# Sheet1.net
KiCad netlist of a schematic drawn in Altium Designer
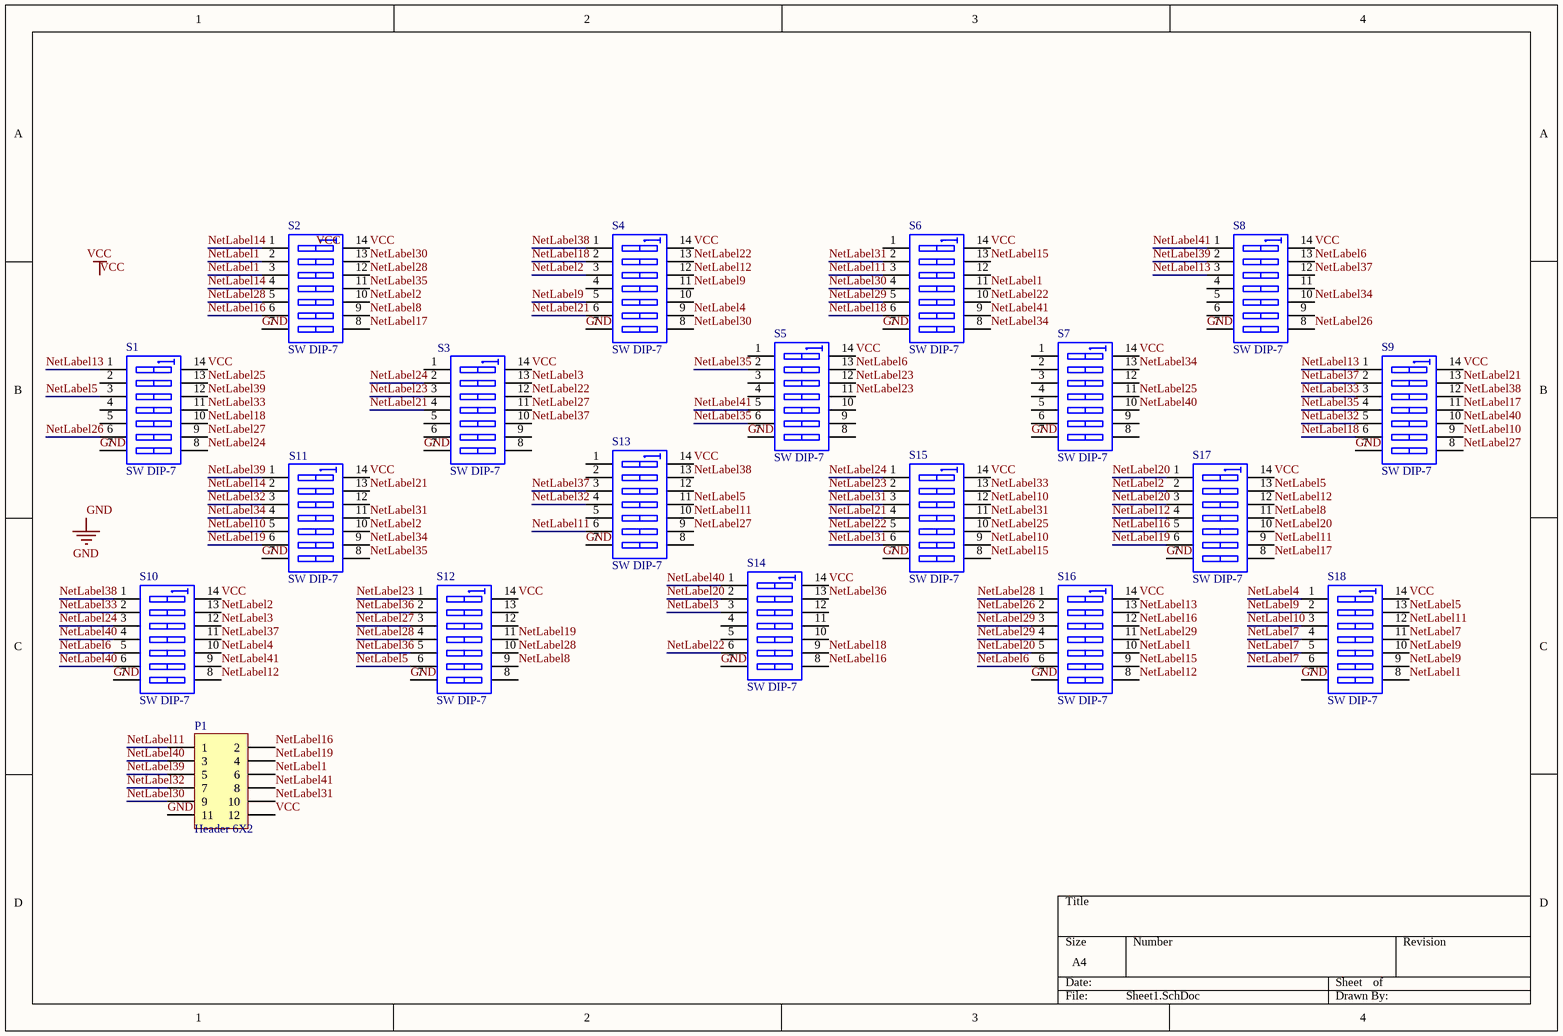
[diagram p0: Sheet1.SchDoc]

(export (version "E")
  (design (tool "Eeschema 10.0.6"))
  (components
    (comp (ref "P1")
      (value "Header 6X2")
      (footprint "HDR2X6")
      (description "Header, 6-Pin, Dual row")
      (fields (field (name "PUBLISHER") "Altium Limited"))
      (libsource (lib "Miscellaneous Connectors") (part "Header 6X2"))
    )
    (comp (ref "S1")
      (value "SW DIP-7")
      (footprint "DIP-14")
      (description "DIP Switch, 7 Position, SPST")
      (fields (field (name "PUBLISHER") "Altium Limited"))
      (libsource (lib "Miscellaneous Devices") (part "SW DIP-7"))
    )
    (comp (ref "S2")
      (value "SW DIP-7")
      (footprint "DIP-14")
      (description "DIP Switch, 7 Position, SPST")
      (fields (field (name "PUBLISHER") "Altium Limited"))
      (libsource (lib "Miscellaneous Devices") (part "SW DIP-7"))
    )
    (comp (ref "S3")
      (value "SW DIP-7")
      (footprint "DIP-14")
      (description "DIP Switch, 7 Position, SPST")
      (fields (field (name "PUBLISHER") "Altium Limited"))
      (libsource (lib "Miscellaneous Devices") (part "SW DIP-7"))
    )
    (comp (ref "S4")
      (value "SW DIP-7")
      (footprint "DIP-14")
      (description "DIP Switch, 7 Position, SPST")
      (fields (field (name "PUBLISHER") "Altium Limited"))
      (libsource (lib "Miscellaneous Devices") (part "SW DIP-7"))
    )
    (comp (ref "S5")
      (value "SW DIP-7")
      (footprint "DIP-14")
      (description "DIP Switch, 7 Position, SPST")
      (fields (field (name "PUBLISHER") "Altium Limited"))
      (libsource (lib "Miscellaneous Devices") (part "SW DIP-7"))
    )
    (comp (ref "S6")
      (value "SW DIP-7")
      (footprint "DIP-14")
      (description "DIP Switch, 7 Position, SPST")
      (fields (field (name "PUBLISHER") "Altium Limited"))
      (libsource (lib "Miscellaneous Devices") (part "SW DIP-7"))
    )
    (comp (ref "S7")
      (value "SW DIP-7")
      (footprint "DIP-14")
      (description "DIP Switch, 7 Position, SPST")
      (fields (field (name "PUBLISHER") "Altium Limited"))
      (libsource (lib "Miscellaneous Devices") (part "SW DIP-7"))
    )
    (comp (ref "S8")
      (value "SW DIP-7")
      (footprint "DIP-14")
      (description "DIP Switch, 7 Position, SPST")
      (fields (field (name "PUBLISHER") "Altium Limited"))
      (libsource (lib "Miscellaneous Devices") (part "SW DIP-7"))
    )
    (comp (ref "S9")
      (value "SW DIP-7")
      (footprint "DIP-14")
      (description "DIP Switch, 7 Position, SPST")
      (fields (field (name "PUBLISHER") "Altium Limited"))
      (libsource (lib "Miscellaneous Devices") (part "SW DIP-7"))
    )
    (comp (ref "S10")
      (value "SW DIP-7")
      (footprint "DIP-14")
      (description "DIP Switch, 7 Position, SPST")
      (fields (field (name "PUBLISHER") "Altium Limited"))
      (libsource (lib "Miscellaneous Devices") (part "SW DIP-7"))
    )
    (comp (ref "S11")
      (value "SW DIP-7")
      (footprint "DIP-14")
      (description "DIP Switch, 7 Position, SPST")
      (fields (field (name "PUBLISHER") "Altium Limited"))
      (libsource (lib "Miscellaneous Devices") (part "SW DIP-7"))
    )
    (comp (ref "S12")
      (value "SW DIP-7")
      (footprint "DIP-14")
      (description "DIP Switch, 7 Position, SPST")
      (fields (field (name "PUBLISHER") "Altium Limited"))
      (libsource (lib "Miscellaneous Devices") (part "SW DIP-7"))
    )
    (comp (ref "S13")
      (value "SW DIP-7")
      (footprint "DIP-14")
      (description "DIP Switch, 7 Position, SPST")
      (fields (field (name "PUBLISHER") "Altium Limited"))
      (libsource (lib "Miscellaneous Devices") (part "SW DIP-7"))
    )
    (comp (ref "S14")
      (value "SW DIP-7")
      (footprint "DIP-14")
      (description "DIP Switch, 7 Position, SPST")
      (fields (field (name "PUBLISHER") "Altium Limited"))
      (libsource (lib "Miscellaneous Devices") (part "SW DIP-7"))
    )
    (comp (ref "S15")
      (value "SW DIP-7")
      (footprint "DIP-14")
      (description "DIP Switch, 7 Position, SPST")
      (fields (field (name "PUBLISHER") "Altium Limited"))
      (libsource (lib "Miscellaneous Devices") (part "SW DIP-7"))
    )
    (comp (ref "S16")
      (value "SW DIP-7")
      (footprint "DIP-14")
      (description "DIP Switch, 7 Position, SPST")
      (fields (field (name "PUBLISHER") "Altium Limited"))
      (libsource (lib "Miscellaneous Devices") (part "SW DIP-7"))
    )
    (comp (ref "S17")
      (value "SW DIP-7")
      (footprint "DIP-14")
      (description "DIP Switch, 7 Position, SPST")
      (fields (field (name "PUBLISHER") "Altium Limited"))
      (libsource (lib "Miscellaneous Devices") (part "SW DIP-7"))
    )
    (comp (ref "S18")
      (value "SW DIP-7")
      (footprint "DIP-14")
      (description "DIP Switch, 7 Position, SPST")
      (fields (field (name "PUBLISHER") "Altium Limited"))
      (libsource (lib "Miscellaneous Devices") (part "SW DIP-7"))
    )
  )
  (nets
    (net (code "1") (name "/NetLabel1") (class "Default")
      (node (ref "P1") (pin "6") (pinfunction "6_6") (pintype "passive"))
      (node (ref "S16") (pin "10") (pinfunction "B5_10") (pintype "passive"))
      (node (ref "S18") (pin "8") (pinfunction "B7_8") (pintype "passive"))
      (node (ref "S2") (pin "2") (pinfunction "A2_2") (pintype "passive"))
      (node (ref "S2") (pin "3") (pinfunction "A3_3") (pintype "passive"))
      (node (ref "S6") (pin "11") (pinfunction "B4_11") (pintype "passive"))
    )
    (net (code "2") (name "/NetLabel2") (class "Default")
      (node (ref "S10") (pin "13") (pinfunction "B2_13") (pintype "passive"))
      (node (ref "S11") (pin "10") (pinfunction "B5_10") (pintype "passive"))
      (node (ref "S17") (pin "2") (pinfunction "A2_2") (pintype "passive"))
      (node (ref "S2") (pin "10") (pinfunction "B5_10") (pintype "passive"))
      (node (ref "S4") (pin "3") (pinfunction "A3_3") (pintype "passive"))
    )
    (net (code "3") (name "/NetLabel3") (class "Default")
      (node (ref "S10") (pin "12") (pinfunction "B3_12") (pintype "passive"))
      (node (ref "S14") (pin "3") (pinfunction "A3_3") (pintype "passive"))
      (node (ref "S3") (pin "13") (pinfunction "B2_13") (pintype "passive"))
    )
    (net (code "4") (name "/NetLabel4") (class "Default")
      (node (ref "S10") (pin "10") (pinfunction "B5_10") (pintype "passive"))
      (node (ref "S18") (pin "1") (pinfunction "A1_1") (pintype "passive"))
      (node (ref "S4") (pin "9") (pinfunction "B6_9") (pintype "passive"))
    )
    (net (code "5") (name "/NetLabel5") (class "Default")
      (node (ref "S1") (pin "3") (pinfunction "A3_3") (pintype "passive"))
      (node (ref "S12") (pin "6") (pinfunction "A6_6") (pintype "passive"))
      (node (ref "S13") (pin "11") (pinfunction "B4_11") (pintype "passive"))
      (node (ref "S17") (pin "13") (pinfunction "B2_13") (pintype "passive"))
      (node (ref "S18") (pin "13") (pinfunction "B2_13") (pintype "passive"))
    )
    (net (code "6") (name "/NetLabel6") (class "Default")
      (node (ref "S10") (pin "5") (pinfunction "A5_5") (pintype "passive"))
      (node (ref "S16") (pin "6") (pinfunction "A6_6") (pintype "passive"))
      (node (ref "S5") (pin "13") (pinfunction "B2_13") (pintype "passive"))
      (node (ref "S8") (pin "13") (pinfunction "B2_13") (pintype "passive"))
    )
    (net (code "7") (name "/NetLabel7") (class "Default")
      (node (ref "S18") (pin "11") (pinfunction "B4_11") (pintype "passive"))
      (node (ref "S18") (pin "4") (pinfunction "A4_4") (pintype "passive"))
      (node (ref "S18") (pin "5") (pinfunction "A5_5") (pintype "passive"))
      (node (ref "S18") (pin "6") (pinfunction "A6_6") (pintype "passive"))
    )
    (net (code "8") (name "/NetLabel8") (class "Default")
      (node (ref "S12") (pin "9") (pinfunction "B6_9") (pintype "passive"))
      (node (ref "S17") (pin "11") (pinfunction "B4_11") (pintype "passive"))
      (node (ref "S2") (pin "9") (pinfunction "B6_9") (pintype "passive"))
    )
    (net (code "9") (name "/NetLabel9") (class "Default")
      (node (ref "S18") (pin "10") (pinfunction "B5_10") (pintype "passive"))
      (node (ref "S18") (pin "2") (pinfunction "A2_2") (pintype "passive"))
      (node (ref "S18") (pin "9") (pinfunction "B6_9") (pintype "passive"))
      (node (ref "S4") (pin "11") (pinfunction "B4_11") (pintype "passive"))
      (node (ref "S4") (pin "5") (pinfunction "A5_5") (pintype "passive"))
    )
    (net (code "10") (name "/NetLabel10") (class "Default")
      (node (ref "S11") (pin "5") (pinfunction "A5_5") (pintype "passive"))
      (node (ref "S15") (pin "12") (pinfunction "B3_12") (pintype "passive"))
      (node (ref "S15") (pin "9") (pinfunction "B6_9") (pintype "passive"))
      (node (ref "S18") (pin "3") (pinfunction "A3_3") (pintype "passive"))
      (node (ref "S9") (pin "9") (pinfunction "B6_9") (pintype "passive"))
    )
    (net (code "11") (name "/NetLabel11") (class "Default")
      (node (ref "P1") (pin "1") (pinfunction "1_1") (pintype "passive"))
      (node (ref "S13") (pin "10") (pinfunction "B5_10") (pintype "passive"))
      (node (ref "S13") (pin "6") (pinfunction "A6_6") (pintype "passive"))
      (node (ref "S17") (pin "9") (pinfunction "B6_9") (pintype "passive"))
      (node (ref "S18") (pin "12") (pinfunction "B3_12") (pintype "passive"))
      (node (ref "S6") (pin "3") (pinfunction "A3_3") (pintype "passive"))
    )
    (net (code "12") (name "/NetLabel12") (class "Default")
      (node (ref "S10") (pin "8") (pinfunction "B7_8") (pintype "passive"))
      (node (ref "S16") (pin "8") (pinfunction "B7_8") (pintype "passive"))
      (node (ref "S17") (pin "12") (pinfunction "B3_12") (pintype "passive"))
      (node (ref "S17") (pin "4") (pinfunction "A4_4") (pintype "passive"))
      (node (ref "S4") (pin "12") (pinfunction "B3_12") (pintype "passive"))
    )
    (net (code "13") (name "/NetLabel13") (class "Default")
      (node (ref "S1") (pin "1") (pinfunction "A1_1") (pintype "passive"))
      (node (ref "S16") (pin "13") (pinfunction "B2_13") (pintype "passive"))
      (node (ref "S8") (pin "3") (pinfunction "A3_3") (pintype "passive"))
      (node (ref "S9") (pin "1") (pinfunction "A1_1") (pintype "passive"))
    )
    (net (code "14") (name "/NetLabel14") (class "Default")
      (node (ref "S11") (pin "2") (pinfunction "A2_2") (pintype "passive"))
      (node (ref "S2") (pin "1") (pinfunction "A1_1") (pintype "passive"))
      (node (ref "S2") (pin "4") (pinfunction "A4_4") (pintype "passive"))
    )
    (net (code "15") (name "/NetLabel15") (class "Default")
      (node (ref "S15") (pin "8") (pinfunction "B7_8") (pintype "passive"))
      (node (ref "S16") (pin "9") (pinfunction "B6_9") (pintype "passive"))
      (node (ref "S6") (pin "13") (pinfunction "B2_13") (pintype "passive"))
    )
    (net (code "16") (name "/NetLabel16") (class "Default")
      (node (ref "P1") (pin "2") (pinfunction "2_2") (pintype "passive"))
      (node (ref "S14") (pin "8") (pinfunction "B7_8") (pintype "passive"))
      (node (ref "S16") (pin "12") (pinfunction "B3_12") (pintype "passive"))
      (node (ref "S17") (pin "5") (pinfunction "A5_5") (pintype "passive"))
      (node (ref "S2") (pin "6") (pinfunction "A6_6") (pintype "passive"))
    )
    (net (code "17") (name "/NetLabel17") (class "Default")
      (node (ref "S17") (pin "8") (pinfunction "B7_8") (pintype "passive"))
      (node (ref "S2") (pin "8") (pinfunction "B7_8") (pintype "passive"))
      (node (ref "S9") (pin "11") (pinfunction "B4_11") (pintype "passive"))
    )
    (net (code "18") (name "/NetLabel18") (class "Default")
      (node (ref "S1") (pin "10") (pinfunction "B5_10") (pintype "passive"))
      (node (ref "S14") (pin "9") (pinfunction "B6_9") (pintype "passive"))
      (node (ref "S4") (pin "2") (pinfunction "A2_2") (pintype "passive"))
      (node (ref "S6") (pin "6") (pinfunction "A6_6") (pintype "passive"))
      (node (ref "S9") (pin "6") (pinfunction "A6_6") (pintype "passive"))
    )
    (net (code "19") (name "/NetLabel19") (class "Default")
      (node (ref "P1") (pin "4") (pinfunction "4_4") (pintype "passive"))
      (node (ref "S11") (pin "6") (pinfunction "A6_6") (pintype "passive"))
      (node (ref "S12") (pin "11") (pinfunction "B4_11") (pintype "passive"))
      (node (ref "S17") (pin "6") (pinfunction "A6_6") (pintype "passive"))
    )
    (net (code "20") (name "/NetLabel20") (class "Default")
      (node (ref "S14") (pin "2") (pinfunction "A2_2") (pintype "passive"))
      (node (ref "S16") (pin "5") (pinfunction "A5_5") (pintype "passive"))
      (node (ref "S17") (pin "1") (pinfunction "A1_1") (pintype "passive"))
      (node (ref "S17") (pin "10") (pinfunction "B5_10") (pintype "passive"))
      (node (ref "S17") (pin "3") (pinfunction "A3_3") (pintype "passive"))
    )
    (net (code "21") (name "/NetLabel21") (class "Default")
      (node (ref "S11") (pin "13") (pinfunction "B2_13") (pintype "passive"))
      (node (ref "S15") (pin "4") (pinfunction "A4_4") (pintype "passive"))
      (node (ref "S3") (pin "4") (pinfunction "A4_4") (pintype "passive"))
      (node (ref "S4") (pin "6") (pinfunction "A6_6") (pintype "passive"))
      (node (ref "S9") (pin "13") (pinfunction "B2_13") (pintype "passive"))
    )
    (net (code "22") (name "/NetLabel22") (class "Default")
      (node (ref "S14") (pin "6") (pinfunction "A6_6") (pintype "passive"))
      (node (ref "S15") (pin "5") (pinfunction "A5_5") (pintype "passive"))
      (node (ref "S3") (pin "12") (pinfunction "B3_12") (pintype "passive"))
      (node (ref "S4") (pin "13") (pinfunction "B2_13") (pintype "passive"))
      (node (ref "S6") (pin "10") (pinfunction "B5_10") (pintype "passive"))
    )
    (net (code "23") (name "/NetLabel23") (class "Default")
      (node (ref "S12") (pin "1") (pinfunction "A1_1") (pintype "passive"))
      (node (ref "S15") (pin "2") (pinfunction "A2_2") (pintype "passive"))
      (node (ref "S3") (pin "3") (pinfunction "A3_3") (pintype "passive"))
      (node (ref "S5") (pin "11") (pinfunction "B4_11") (pintype "passive"))
      (node (ref "S5") (pin "12") (pinfunction "B3_12") (pintype "passive"))
    )
    (net (code "24") (name "/NetLabel24") (class "Default")
      (node (ref "S1") (pin "8") (pinfunction "B7_8") (pintype "passive"))
      (node (ref "S10") (pin "3") (pinfunction "A3_3") (pintype "passive"))
      (node (ref "S15") (pin "1") (pinfunction "A1_1") (pintype "passive"))
      (node (ref "S3") (pin "2") (pinfunction "A2_2") (pintype "passive"))
    )
    (net (code "25") (name "/NetLabel25") (class "Default")
      (node (ref "S1") (pin "13") (pinfunction "B2_13") (pintype "passive"))
      (node (ref "S15") (pin "10") (pinfunction "B5_10") (pintype "passive"))
      (node (ref "S7") (pin "11") (pinfunction "B4_11") (pintype "passive"))
    )
    (net (code "26") (name "/NetLabel26") (class "Default")
      (node (ref "S1") (pin "6") (pinfunction "A6_6") (pintype "passive"))
      (node (ref "S16") (pin "2") (pinfunction "A2_2") (pintype "passive"))
      (node (ref "S8") (pin "8") (pinfunction "B7_8") (pintype "passive"))
    )
    (net (code "27") (name "/NetLabel27") (class "Default")
      (node (ref "S1") (pin "9") (pinfunction "B6_9") (pintype "passive"))
      (node (ref "S12") (pin "3") (pinfunction "A3_3") (pintype "passive"))
      (node (ref "S13") (pin "9") (pinfunction "B6_9") (pintype "passive"))
      (node (ref "S3") (pin "11") (pinfunction "B4_11") (pintype "passive"))
      (node (ref "S9") (pin "8") (pinfunction "B7_8") (pintype "passive"))
    )
    (net (code "28") (name "/NetLabel28") (class "Default")
      (node (ref "S12") (pin "10") (pinfunction "B5_10") (pintype "passive"))
      (node (ref "S12") (pin "4") (pinfunction "A4_4") (pintype "passive"))
      (node (ref "S16") (pin "1") (pinfunction "A1_1") (pintype "passive"))
      (node (ref "S2") (pin "12") (pinfunction "B3_12") (pintype "passive"))
      (node (ref "S2") (pin "5") (pinfunction "A5_5") (pintype "passive"))
    )
    (net (code "29") (name "/NetLabel29") (class "Default")
      (node (ref "S16") (pin "11") (pinfunction "B4_11") (pintype "passive"))
      (node (ref "S16") (pin "3") (pinfunction "A3_3") (pintype "passive"))
      (node (ref "S16") (pin "4") (pinfunction "A4_4") (pintype "passive"))
      (node (ref "S6") (pin "5") (pinfunction "A5_5") (pintype "passive"))
    )
    (net (code "30") (name "/NetLabel30") (class "Default")
      (node (ref "P1") (pin "9") (pinfunction "9_9") (pintype "passive"))
      (node (ref "S2") (pin "13") (pinfunction "B2_13") (pintype "passive"))
      (node (ref "S4") (pin "8") (pinfunction "B7_8") (pintype "passive"))
      (node (ref "S6") (pin "4") (pinfunction "A4_4") (pintype "passive"))
    )
    (net (code "31") (name "/NetLabel31") (class "Default")
      (node (ref "P1") (pin "10") (pinfunction "10_10") (pintype "passive"))
      (node (ref "S11") (pin "11") (pinfunction "B4_11") (pintype "passive"))
      (node (ref "S15") (pin "11") (pinfunction "B4_11") (pintype "passive"))
      (node (ref "S15") (pin "3") (pinfunction "A3_3") (pintype "passive"))
      (node (ref "S15") (pin "6") (pinfunction "A6_6") (pintype "passive"))
      (node (ref "S6") (pin "2") (pinfunction "A2_2") (pintype "passive"))
    )
    (net (code "32") (name "/NetLabel32") (class "Default")
      (node (ref "P1") (pin "7") (pinfunction "7_7") (pintype "passive"))
      (node (ref "S11") (pin "3") (pinfunction "A3_3") (pintype "passive"))
      (node (ref "S13") (pin "4") (pinfunction "A4_4") (pintype "passive"))
      (node (ref "S9") (pin "5") (pinfunction "A5_5") (pintype "passive"))
    )
    (net (code "33") (name "/NetLabel33") (class "Default")
      (node (ref "S1") (pin "11") (pinfunction "B4_11") (pintype "passive"))
      (node (ref "S10") (pin "2") (pinfunction "A2_2") (pintype "passive"))
      (node (ref "S15") (pin "13") (pinfunction "B2_13") (pintype "passive"))
      (node (ref "S9") (pin "3") (pinfunction "A3_3") (pintype "passive"))
    )
    (net (code "34") (name "/NetLabel34") (class "Default")
      (node (ref "S11") (pin "4") (pinfunction "A4_4") (pintype "passive"))
      (node (ref "S11") (pin "9") (pinfunction "B6_9") (pintype "passive"))
      (node (ref "S6") (pin "8") (pinfunction "B7_8") (pintype "passive"))
      (node (ref "S7") (pin "13") (pinfunction "B2_13") (pintype "passive"))
      (node (ref "S8") (pin "10") (pinfunction "B5_10") (pintype "passive"))
    )
    (net (code "35") (name "/NetLabel35") (class "Default")
      (node (ref "S11") (pin "8") (pinfunction "B7_8") (pintype "passive"))
      (node (ref "S2") (pin "11") (pinfunction "B4_11") (pintype "passive"))
      (node (ref "S5") (pin "2") (pinfunction "A2_2") (pintype "passive"))
      (node (ref "S5") (pin "6") (pinfunction "A6_6") (pintype "passive"))
      (node (ref "S9") (pin "4") (pinfunction "A4_4") (pintype "passive"))
    )
    (net (code "36") (name "/NetLabel36") (class "Default")
      (node (ref "S12") (pin "2") (pinfunction "A2_2") (pintype "passive"))
      (node (ref "S12") (pin "5") (pinfunction "A5_5") (pintype "passive"))
      (node (ref "S14") (pin "13") (pinfunction "B2_13") (pintype "passive"))
    )
    (net (code "37") (name "/NetLabel37") (class "Default")
      (node (ref "S10") (pin "11") (pinfunction "B4_11") (pintype "passive"))
      (node (ref "S13") (pin "3") (pinfunction "A3_3") (pintype "passive"))
      (node (ref "S3") (pin "10") (pinfunction "B5_10") (pintype "passive"))
      (node (ref "S8") (pin "12") (pinfunction "B3_12") (pintype "passive"))
      (node (ref "S9") (pin "2") (pinfunction "A2_2") (pintype "passive"))
    )
    (net (code "38") (name "/NetLabel38") (class "Default")
      (node (ref "S10") (pin "1") (pinfunction "A1_1") (pintype "passive"))
      (node (ref "S13") (pin "13") (pinfunction "B2_13") (pintype "passive"))
      (node (ref "S4") (pin "1") (pinfunction "A1_1") (pintype "passive"))
      (node (ref "S9") (pin "12") (pinfunction "B3_12") (pintype "passive"))
    )
    (net (code "39") (name "/NetLabel39") (class "Default")
      (node (ref "P1") (pin "5") (pinfunction "5_5") (pintype "passive"))
      (node (ref "S1") (pin "12") (pinfunction "B3_12") (pintype "passive"))
      (node (ref "S11") (pin "1") (pinfunction "A1_1") (pintype "passive"))
      (node (ref "S8") (pin "2") (pinfunction "A2_2") (pintype "passive"))
    )
    (net (code "40") (name "/NetLabel40") (class "Default")
      (node (ref "P1") (pin "3") (pinfunction "3_3") (pintype "passive"))
      (node (ref "S10") (pin "4") (pinfunction "A4_4") (pintype "passive"))
      (node (ref "S10") (pin "6") (pinfunction "A6_6") (pintype "passive"))
      (node (ref "S14") (pin "1") (pinfunction "A1_1") (pintype "passive"))
      (node (ref "S7") (pin "10") (pinfunction "B5_10") (pintype "passive"))
      (node (ref "S9") (pin "10") (pinfunction "B5_10") (pintype "passive"))
    )
    (net (code "41") (name "/NetLabel41") (class "Default")
      (node (ref "P1") (pin "8") (pinfunction "8_8") (pintype "passive"))
      (node (ref "S10") (pin "9") (pinfunction "B6_9") (pintype "passive"))
      (node (ref "S5") (pin "5") (pinfunction "A5_5") (pintype "passive"))
      (node (ref "S6") (pin "9") (pinfunction "B6_9") (pintype "passive"))
      (node (ref "S8") (pin "1") (pinfunction "A1_1") (pintype "passive"))
    )
    (net (code "42") (name "GND") (class "Default")
      (node (ref "P1") (pin "11") (pinfunction "11_11") (pintype "passive"))
      (node (ref "S1") (pin "7") (pinfunction "A7_7") (pintype "passive"))
      (node (ref "S10") (pin "7") (pinfunction "A7_7") (pintype "passive"))
      (node (ref "S11") (pin "7") (pinfunction "A7_7") (pintype "passive"))
      (node (ref "S12") (pin "7") (pinfunction "A7_7") (pintype "passive"))
      (node (ref "S13") (pin "7") (pinfunction "A7_7") (pintype "passive"))
      (node (ref "S14") (pin "7") (pinfunction "A7_7") (pintype "passive"))
      (node (ref "S15") (pin "7") (pinfunction "A7_7") (pintype "passive"))
      (node (ref "S16") (pin "7") (pinfunction "A7_7") (pintype "passive"))
      (node (ref "S17") (pin "7") (pinfunction "A7_7") (pintype "passive"))
      (node (ref "S18") (pin "7") (pinfunction "A7_7") (pintype "passive"))
      (node (ref "S2") (pin "7") (pinfunction "A7_7") (pintype "passive"))
      (node (ref "S3") (pin "7") (pinfunction "A7_7") (pintype "passive"))
      (node (ref "S4") (pin "7") (pinfunction "A7_7") (pintype "passive"))
      (node (ref "S5") (pin "7") (pinfunction "A7_7") (pintype "passive"))
      (node (ref "S6") (pin "7") (pinfunction "A7_7") (pintype "passive"))
      (node (ref "S7") (pin "7") (pinfunction "A7_7") (pintype "passive"))
      (node (ref "S8") (pin "7") (pinfunction "A7_7") (pintype "passive"))
      (node (ref "S9") (pin "7") (pinfunction "A7_7") (pintype "passive"))
    )
    (net (code "43") (name "VCC") (class "Default")
      (node (ref "P1") (pin "12") (pinfunction "12_12") (pintype "passive"))
      (node (ref "S1") (pin "14") (pinfunction "B1_14") (pintype "passive"))
      (node (ref "S10") (pin "14") (pinfunction "B1_14") (pintype "passive"))
      (node (ref "S11") (pin "14") (pinfunction "B1_14") (pintype "passive"))
      (node (ref "S12") (pin "14") (pinfunction "B1_14") (pintype "passive"))
      (node (ref "S13") (pin "14") (pinfunction "B1_14") (pintype "passive"))
      (node (ref "S14") (pin "14") (pinfunction "B1_14") (pintype "passive"))
      (node (ref "S15") (pin "14") (pinfunction "B1_14") (pintype "passive"))
      (node (ref "S16") (pin "14") (pinfunction "B1_14") (pintype "passive"))
      (node (ref "S17") (pin "14") (pinfunction "B1_14") (pintype "passive"))
      (node (ref "S18") (pin "14") (pinfunction "B1_14") (pintype "passive"))
      (node (ref "S2") (pin "14") (pinfunction "B1_14") (pintype "passive"))
      (node (ref "S3") (pin "14") (pinfunction "B1_14") (pintype "passive"))
      (node (ref "S4") (pin "14") (pinfunction "B1_14") (pintype "passive"))
      (node (ref "S5") (pin "14") (pinfunction "B1_14") (pintype "passive"))
      (node (ref "S6") (pin "14") (pinfunction "B1_14") (pintype "passive"))
      (node (ref "S7") (pin "14") (pinfunction "B1_14") (pintype "passive"))
      (node (ref "S8") (pin "14") (pinfunction "B1_14") (pintype "passive"))
      (node (ref "S9") (pin "14") (pinfunction "B1_14") (pintype "passive"))
    )
    (net (code "44") (name "unconnected-(S1-A2-Pad2)") (class "Default")
      (node (ref "S1") (pin "2") (pinfunction "A2_2") (pintype "passive"))
    )
    (net (code "45") (name "unconnected-(S1-A4-Pad4)") (class "Default")
      (node (ref "S1") (pin "4") (pinfunction "A4_4") (pintype "passive"))
    )
    (net (code "46") (name "unconnected-(S1-A5-Pad5)") (class "Default")
      (node (ref "S1") (pin "5") (pinfunction "A5_5") (pintype "passive"))
    )
    (net (code "47") (name "unconnected-(S3-A1-Pad1)") (class "Default")
      (node (ref "S3") (pin "1") (pinfunction "A1_1") (pintype "passive"))
    )
    (net (code "48") (name "unconnected-(S3-A5-Pad5)") (class "Default")
      (node (ref "S3") (pin "5") (pinfunction "A5_5") (pintype "passive"))
    )
    (net (code "49") (name "unconnected-(S3-A6-Pad6)") (class "Default")
      (node (ref "S3") (pin "6") (pinfunction "A6_6") (pintype "passive"))
    )
    (net (code "50") (name "unconnected-(S3-B6-Pad9)") (class "Default")
      (node (ref "S3") (pin "9") (pinfunction "B6_9") (pintype "passive"))
    )
    (net (code "51") (name "unconnected-(S3-B7-Pad8)") (class "Default")
      (node (ref "S3") (pin "8") (pinfunction "B7_8") (pintype "passive"))
    )
    (net (code "52") (name "unconnected-(S4-A4-Pad4)") (class "Default")
      (node (ref "S4") (pin "4") (pinfunction "A4_4") (pintype "passive"))
    )
    (net (code "53") (name "unconnected-(S4-B5-Pad10)") (class "Default")
      (node (ref "S4") (pin "10") (pinfunction "B5_10") (pintype "passive"))
    )
    (net (code "54") (name "unconnected-(S5-A1-Pad1)") (class "Default")
      (node (ref "S5") (pin "1") (pinfunction "A1_1") (pintype "passive"))
    )
    (net (code "55") (name "unconnected-(S5-A3-Pad3)") (class "Default")
      (node (ref "S5") (pin "3") (pinfunction "A3_3") (pintype "passive"))
    )
    (net (code "56") (name "unconnected-(S5-A4-Pad4)") (class "Default")
      (node (ref "S5") (pin "4") (pinfunction "A4_4") (pintype "passive"))
    )
    (net (code "57") (name "unconnected-(S5-B5-Pad10)") (class "Default")
      (node (ref "S5") (pin "10") (pinfunction "B5_10") (pintype "passive"))
    )
    (net (code "58") (name "unconnected-(S5-B6-Pad9)") (class "Default")
      (node (ref "S5") (pin "9") (pinfunction "B6_9") (pintype "passive"))
    )
    (net (code "59") (name "unconnected-(S5-B7-Pad8)") (class "Default")
      (node (ref "S5") (pin "8") (pinfunction "B7_8") (pintype "passive"))
    )
    (net (code "60") (name "unconnected-(S6-A1-Pad1)") (class "Default")
      (node (ref "S6") (pin "1") (pinfunction "A1_1") (pintype "passive"))
    )
    (net (code "61") (name "unconnected-(S6-B3-Pad12)") (class "Default")
      (node (ref "S6") (pin "12") (pinfunction "B3_12") (pintype "passive"))
    )
    (net (code "62") (name "unconnected-(S7-A1-Pad1)") (class "Default")
      (node (ref "S7") (pin "1") (pinfunction "A1_1") (pintype "passive"))
    )
    (net (code "63") (name "unconnected-(S7-A2-Pad2)") (class "Default")
      (node (ref "S7") (pin "2") (pinfunction "A2_2") (pintype "passive"))
    )
    (net (code "64") (name "unconnected-(S7-A3-Pad3)") (class "Default")
      (node (ref "S7") (pin "3") (pinfunction "A3_3") (pintype "passive"))
    )
    (net (code "65") (name "unconnected-(S7-A4-Pad4)") (class "Default")
      (node (ref "S7") (pin "4") (pinfunction "A4_4") (pintype "passive"))
    )
    (net (code "66") (name "unconnected-(S7-A5-Pad5)") (class "Default")
      (node (ref "S7") (pin "5") (pinfunction "A5_5") (pintype "passive"))
    )
    (net (code "67") (name "unconnected-(S7-A6-Pad6)") (class "Default")
      (node (ref "S7") (pin "6") (pinfunction "A6_6") (pintype "passive"))
    )
    (net (code "68") (name "unconnected-(S7-B3-Pad12)") (class "Default")
      (node (ref "S7") (pin "12") (pinfunction "B3_12") (pintype "passive"))
    )
    (net (code "69") (name "unconnected-(S7-B6-Pad9)") (class "Default")
      (node (ref "S7") (pin "9") (pinfunction "B6_9") (pintype "passive"))
    )
    (net (code "70") (name "unconnected-(S7-B7-Pad8)") (class "Default")
      (node (ref "S7") (pin "8") (pinfunction "B7_8") (pintype "passive"))
    )
    (net (code "71") (name "unconnected-(S8-A4-Pad4)") (class "Default")
      (node (ref "S8") (pin "4") (pinfunction "A4_4") (pintype "passive"))
    )
    (net (code "72") (name "unconnected-(S8-A5-Pad5)") (class "Default")
      (node (ref "S8") (pin "5") (pinfunction "A5_5") (pintype "passive"))
    )
    (net (code "73") (name "unconnected-(S8-A6-Pad6)") (class "Default")
      (node (ref "S8") (pin "6") (pinfunction "A6_6") (pintype "passive"))
    )
    (net (code "74") (name "unconnected-(S8-B4-Pad11)") (class "Default")
      (node (ref "S8") (pin "11") (pinfunction "B4_11") (pintype "passive"))
    )
    (net (code "75") (name "unconnected-(S8-B6-Pad9)") (class "Default")
      (node (ref "S8") (pin "9") (pinfunction "B6_9") (pintype "passive"))
    )
    (net (code "76") (name "unconnected-(S11-B3-Pad12)") (class "Default")
      (node (ref "S11") (pin "12") (pinfunction "B3_12") (pintype "passive"))
    )
    (net (code "77") (name "unconnected-(S12-B2-Pad13)") (class "Default")
      (node (ref "S12") (pin "13") (pinfunction "B2_13") (pintype "passive"))
    )
    (net (code "78") (name "unconnected-(S12-B3-Pad12)") (class "Default")
      (node (ref "S12") (pin "12") (pinfunction "B3_12") (pintype "passive"))
    )
    (net (code "79") (name "unconnected-(S12-B7-Pad8)") (class "Default")
      (node (ref "S12") (pin "8") (pinfunction "B7_8") (pintype "passive"))
    )
    (net (code "80") (name "unconnected-(S13-A1-Pad1)") (class "Default")
      (node (ref "S13") (pin "1") (pinfunction "A1_1") (pintype "passive"))
    )
    (net (code "81") (name "unconnected-(S13-A2-Pad2)") (class "Default")
      (node (ref "S13") (pin "2") (pinfunction "A2_2") (pintype "passive"))
    )
    (net (code "82") (name "unconnected-(S13-A5-Pad5)") (class "Default")
      (node (ref "S13") (pin "5") (pinfunction "A5_5") (pintype "passive"))
    )
    (net (code "83") (name "unconnected-(S13-B3-Pad12)") (class "Default")
      (node (ref "S13") (pin "12") (pinfunction "B3_12") (pintype "passive"))
    )
    (net (code "84") (name "unconnected-(S13-B7-Pad8)") (class "Default")
      (node (ref "S13") (pin "8") (pinfunction "B7_8") (pintype "passive"))
    )
    (net (code "85") (name "unconnected-(S14-A4-Pad4)") (class "Default")
      (node (ref "S14") (pin "4") (pinfunction "A4_4") (pintype "passive"))
    )
    (net (code "86") (name "unconnected-(S14-A5-Pad5)") (class "Default")
      (node (ref "S14") (pin "5") (pinfunction "A5_5") (pintype "passive"))
    )
    (net (code "87") (name "unconnected-(S14-B3-Pad12)") (class "Default")
      (node (ref "S14") (pin "12") (pinfunction "B3_12") (pintype "passive"))
    )
    (net (code "88") (name "unconnected-(S14-B4-Pad11)") (class "Default")
      (node (ref "S14") (pin "11") (pinfunction "B4_11") (pintype "passive"))
    )
    (net (code "89") (name "unconnected-(S14-B5-Pad10)") (class "Default")
      (node (ref "S14") (pin "10") (pinfunction "B5_10") (pintype "passive"))
    )
  )
)
